# RH018_2.net
KiCad netlist of a schematic drawn in EAGLE
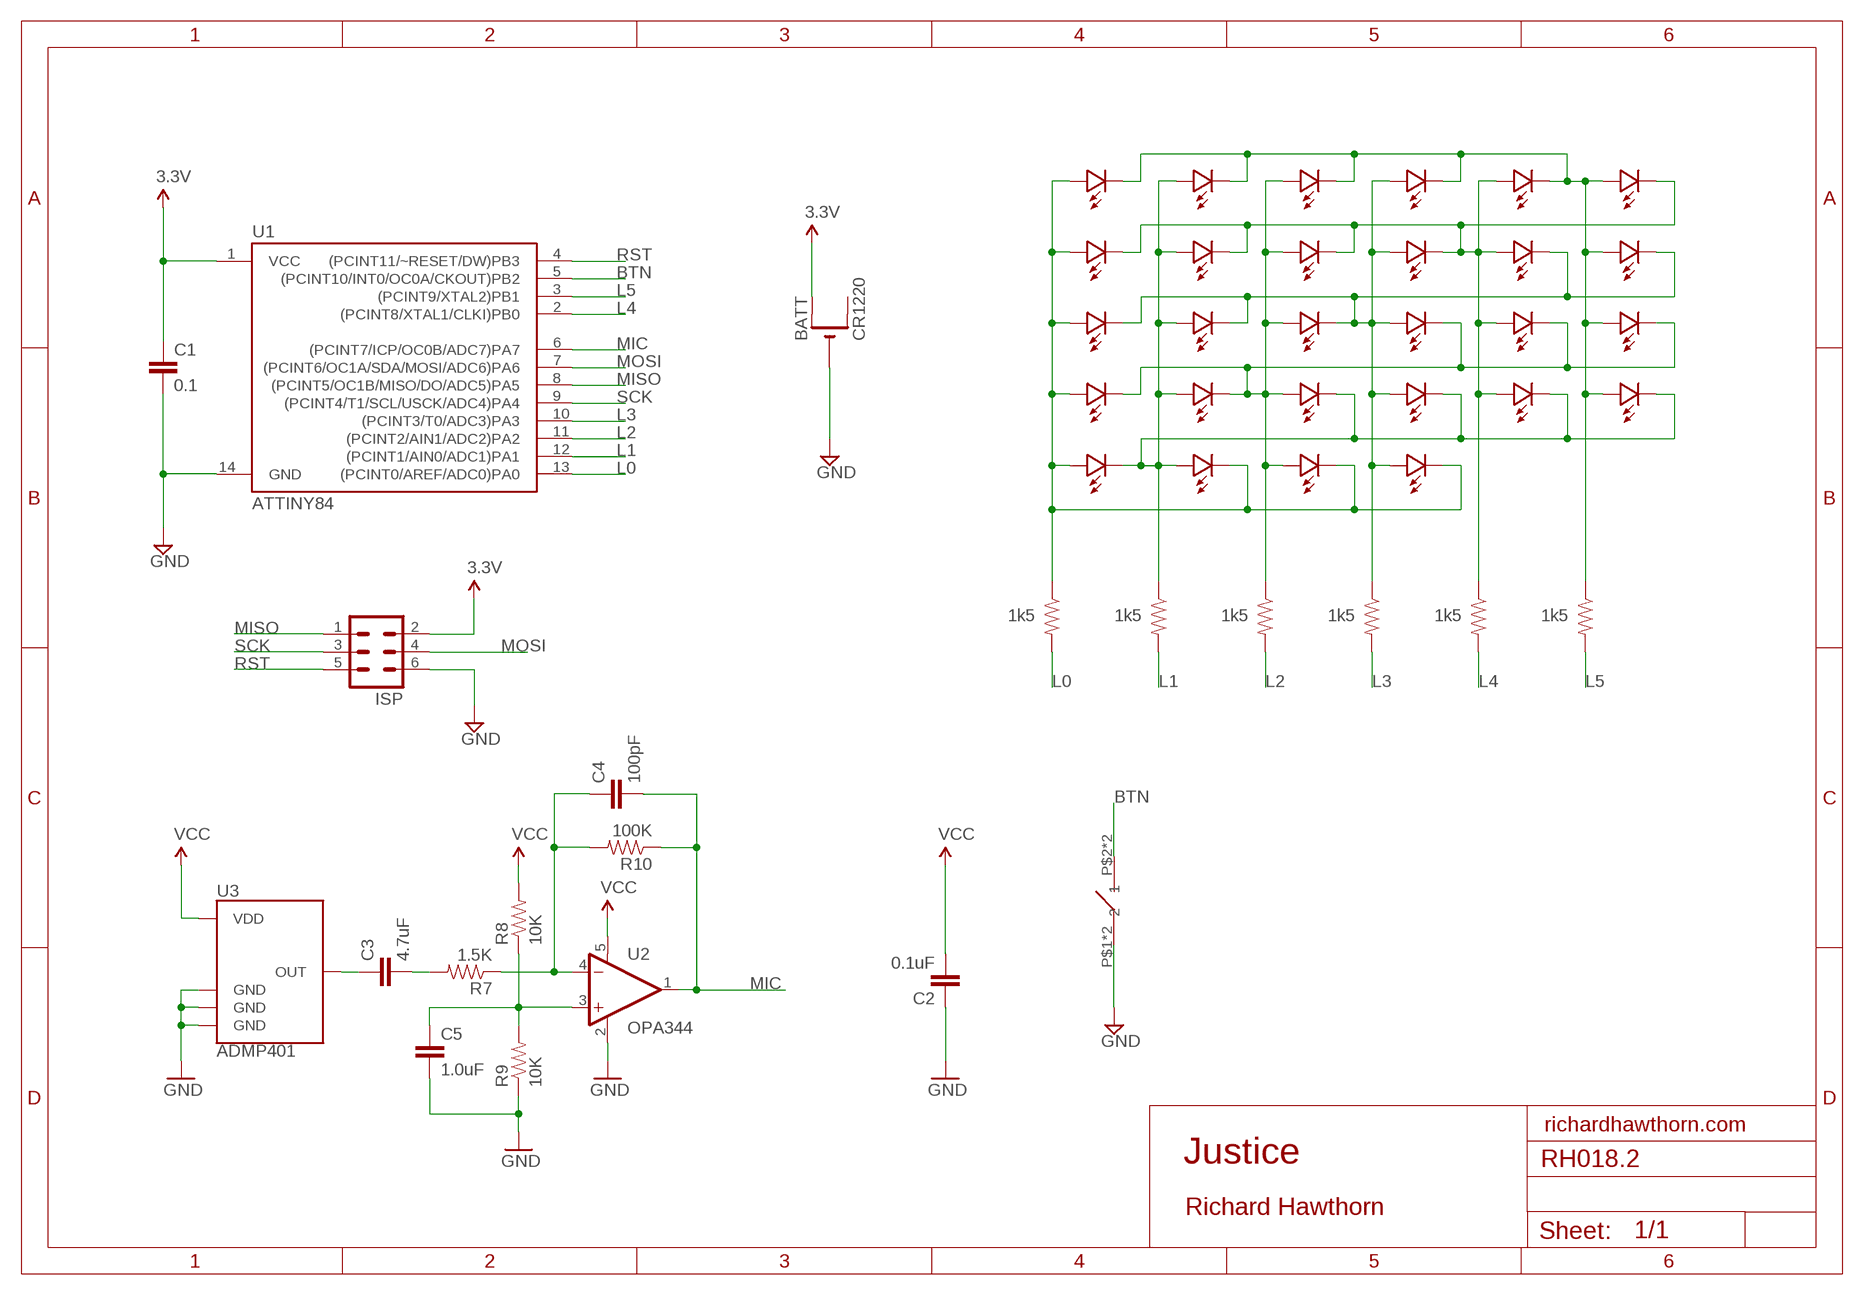
[diagram p0: schematic, sheet 1]

(export (version "E")
  (design (tool "Eeschema 10.0.6"))
  (components
    (comp (ref "BATT")
      (value "CR1220")
      (footprint "eagle-import:CR1220-SMD")
      (libsource (lib "eagle-import") (part "CR1220SMT"))
    )
    (comp (ref "BTN1")
      (value "TURTLE-3PIN")
      (footprint "eagle-import:TURTLE-3PIN")
      (libsource (lib "eagle-import") (part "TURTLE-3PIN"))
    )
    (comp (ref "C1")
      (value "0.1")
      (footprint "eagle-import:0603-CAP")
      (libsource (lib "eagle-import") (part "CAP0603-CAP"))
    )
    (comp (ref "C2")
      (value "0.1uF")
      (footprint "eagle-import:0402-CAP")
      (libsource (lib "eagle-import") (part "SparkFun_CAP0402-CAP"))
    )
    (comp (ref "C3")
      (value "4.7uF")
      (footprint "eagle-import:0402-CAP")
      (libsource (lib "eagle-import") (part "SparkFun_CAP0402-CAP"))
    )
    (comp (ref "C4")
      (value "100pF")
      (footprint "eagle-import:0402-CAP")
      (libsource (lib "eagle-import") (part "SparkFun_CAP0402-CAP"))
    )
    (comp (ref "C5")
      (value "1.0uF")
      (footprint "eagle-import:0402-CAP")
      (libsource (lib "eagle-import") (part "SparkFun_CAP0402-CAP"))
    )
    (comp (ref "ISP")
      (value "MA03-2")
      (footprint "eagle-import:MA03-2")
      (libsource (lib "eagle-import") (part "MA03-2"))
    )
    (comp (ref "LED1")
      (value "LED0603")
      (footprint "eagle-import:0603-LED")
      (libsource (lib "eagle-import") (part "LED0603"))
    )
    (comp (ref "LED2")
      (value "LED0603")
      (footprint "eagle-import:0603-LED")
      (libsource (lib "eagle-import") (part "LED0603"))
    )
    (comp (ref "LED3")
      (value "LED0603")
      (footprint "eagle-import:0603-LED")
      (libsource (lib "eagle-import") (part "LED0603"))
    )
    (comp (ref "LED4")
      (value "LED0603")
      (footprint "eagle-import:0603-LED")
      (libsource (lib "eagle-import") (part "LED0603"))
    )
    (comp (ref "LED5")
      (value "LED0603")
      (footprint "eagle-import:0603-LED")
      (libsource (lib "eagle-import") (part "LED0603"))
    )
    (comp (ref "LED6")
      (value "LED0603")
      (footprint "eagle-import:0603-LED")
      (libsource (lib "eagle-import") (part "LED0603"))
    )
    (comp (ref "LED7")
      (value "LED0603")
      (footprint "eagle-import:0603-LED")
      (libsource (lib "eagle-import") (part "LED0603"))
    )
    (comp (ref "LED8")
      (value "LED0603")
      (footprint "eagle-import:0603-LED")
      (libsource (lib "eagle-import") (part "LED0603"))
    )
    (comp (ref "LED9")
      (value "LED0603")
      (footprint "eagle-import:0603-LED")
      (libsource (lib "eagle-import") (part "LED0603"))
    )
    (comp (ref "LED10")
      (value "LED0603")
      (footprint "eagle-import:0603-LED")
      (libsource (lib "eagle-import") (part "LED0603"))
    )
    (comp (ref "LED11")
      (value "LED0603")
      (footprint "eagle-import:0603-LED")
      (libsource (lib "eagle-import") (part "LED0603"))
    )
    (comp (ref "LED12")
      (value "LED0603")
      (footprint "eagle-import:0603-LED")
      (libsource (lib "eagle-import") (part "LED0603"))
    )
    (comp (ref "LED13")
      (value "LED0603")
      (footprint "eagle-import:0603-LED")
      (libsource (lib "eagle-import") (part "LED0603"))
    )
    (comp (ref "LED14")
      (value "LED0603")
      (footprint "eagle-import:0603-LED")
      (libsource (lib "eagle-import") (part "LED0603"))
    )
    (comp (ref "LED15")
      (value "LED0603")
      (footprint "eagle-import:0603-LED")
      (libsource (lib "eagle-import") (part "LED0603"))
    )
    (comp (ref "LED16")
      (value "LED0603")
      (footprint "eagle-import:0603-LED")
      (libsource (lib "eagle-import") (part "LED0603"))
    )
    (comp (ref "LED17")
      (value "LED0603")
      (footprint "eagle-import:0603-LED")
      (libsource (lib "eagle-import") (part "LED0603"))
    )
    (comp (ref "LED18")
      (value "LED0603")
      (footprint "eagle-import:0603-LED")
      (libsource (lib "eagle-import") (part "LED0603"))
    )
    (comp (ref "LED19")
      (value "LED0603")
      (footprint "eagle-import:0603-LED")
      (libsource (lib "eagle-import") (part "LED0603"))
    )
    (comp (ref "LED20")
      (value "LED0603")
      (footprint "eagle-import:0603-LED")
      (libsource (lib "eagle-import") (part "LED0603"))
    )
    (comp (ref "LED21")
      (value "LED0603")
      (footprint "eagle-import:0603-LED")
      (libsource (lib "eagle-import") (part "LED0603"))
    )
    (comp (ref "LED22")
      (value "LED0603")
      (footprint "eagle-import:0603-LED")
      (libsource (lib "eagle-import") (part "LED0603"))
    )
    (comp (ref "LED23")
      (value "LED0603")
      (footprint "eagle-import:0603-LED")
      (libsource (lib "eagle-import") (part "LED0603"))
    )
    (comp (ref "LED24")
      (value "LED0603")
      (footprint "eagle-import:0603-LED")
      (libsource (lib "eagle-import") (part "LED0603"))
    )
    (comp (ref "LED25")
      (value "LED0603")
      (footprint "eagle-import:0603-LED")
      (libsource (lib "eagle-import") (part "LED0603"))
    )
    (comp (ref "LED26")
      (value "LED0603")
      (footprint "eagle-import:0603-LED")
      (libsource (lib "eagle-import") (part "LED0603"))
    )
    (comp (ref "LED27")
      (value "LED0603")
      (footprint "eagle-import:0603-LED")
      (libsource (lib "eagle-import") (part "LED0603"))
    )
    (comp (ref "LED28")
      (value "LED0603")
      (footprint "eagle-import:0603-LED")
      (libsource (lib "eagle-import") (part "LED0603"))
    )
    (comp (ref "R1")
      (value "1k5")
      (footprint "eagle-import:0603-RES")
      (libsource (lib "eagle-import") (part "RESISTOR0603-RES"))
    )
    (comp (ref "R2")
      (value "1k5")
      (footprint "eagle-import:0603-RES")
      (libsource (lib "eagle-import") (part "RESISTOR0603-RES"))
    )
    (comp (ref "R3")
      (value "1k5")
      (footprint "eagle-import:0603-RES")
      (libsource (lib "eagle-import") (part "RESISTOR0603-RES"))
    )
    (comp (ref "R4")
      (value "1k5")
      (footprint "eagle-import:0603-RES")
      (libsource (lib "eagle-import") (part "RESISTOR0603-RES"))
    )
    (comp (ref "R5")
      (value "1k5")
      (footprint "eagle-import:0603-RES")
      (libsource (lib "eagle-import") (part "RESISTOR0603-RES"))
    )
    (comp (ref "R6")
      (value "1k5")
      (footprint "eagle-import:0603-RES")
      (libsource (lib "eagle-import") (part "RESISTOR0603-RES"))
    )
    (comp (ref "R7")
      (value "1.5K")
      (footprint "eagle-import:0402-RES")
      (libsource (lib "eagle-import") (part "SparkFun_RESISTOR0402-RES"))
    )
    (comp (ref "R8")
      (value "10K")
      (footprint "eagle-import:0402-RES")
      (libsource (lib "eagle-import") (part "SparkFun_RESISTOR0402-RES"))
    )
    (comp (ref "R9")
      (value "10K")
      (footprint "eagle-import:0402-RES")
      (libsource (lib "eagle-import") (part "SparkFun_RESISTOR0402-RES"))
    )
    (comp (ref "R10")
      (value "100K")
      (footprint "eagle-import:0402-RES")
      (libsource (lib "eagle-import") (part "SparkFun_RESISTOR0402-RES"))
    )
    (comp (ref "U1")
      (value "ATTINY84")
      (footprint "eagle-import:SO14")
      (libsource (lib "eagle-import") (part "ATTINY84"))
    )
    (comp (ref "U2")
      (value "OPA344")
      (footprint "eagle-import:SOT23-5")
      (libsource (lib "eagle-import") (part "OPA344"))
    )
    (comp (ref "U3")
      (value "ADMP401")
      (footprint "eagle-import:ADMP401")
      (libsource (lib "eagle-import") (part "ADMP401"))
    )
  )
  (nets
    (net (code "1") (name "/BTN") (class "Default")
      (node (ref "BTN1") (pin "P$2") (pinfunction "2_P$2") (pintype "bidirectional"))
      (node (ref "BTN1") (pin "P$4") (pinfunction "2_P$4") (pintype "bidirectional"))
      (node (ref "U1") (pin "5") (pinfunction "(PCINT10/INT0/OC0A/CKOUT)PB2_5") (pintype "bidirectional"))
    )
    (net (code "2") (name "/L0") (class "Default")
      (node (ref "R1") (pin "2") (pinfunction "2_2") (pintype "passive"))
      (node (ref "U1") (pin "13") (pinfunction "(PCINT0/AREF/ADC0)PA0_13") (pintype "bidirectional"))
    )
    (net (code "3") (name "/L1") (class "Default")
      (node (ref "R2") (pin "2") (pinfunction "2_2") (pintype "passive"))
      (node (ref "U1") (pin "12") (pinfunction "(PCINT1/AIN0/ADC1)PA1_12") (pintype "bidirectional"))
    )
    (net (code "4") (name "/L2") (class "Default")
      (node (ref "R3") (pin "2") (pinfunction "2_2") (pintype "passive"))
      (node (ref "U1") (pin "11") (pinfunction "(PCINT2/AIN1/ADC2)PA2_11") (pintype "bidirectional"))
    )
    (net (code "5") (name "/L3") (class "Default")
      (node (ref "R4") (pin "2") (pinfunction "2_2") (pintype "passive"))
      (node (ref "U1") (pin "10") (pinfunction "(PCINT3/T0/ADC3)PA3_10") (pintype "bidirectional"))
    )
    (net (code "6") (name "/L4") (class "Default")
      (node (ref "R5") (pin "2") (pinfunction "2_2") (pintype "passive"))
      (node (ref "U1") (pin "2") (pinfunction "(PCINT8/XTAL1/CLKI)PB0_2") (pintype "bidirectional"))
    )
    (net (code "7") (name "/L5") (class "Default")
      (node (ref "R6") (pin "2") (pinfunction "2_2") (pintype "passive"))
      (node (ref "U1") (pin "3") (pinfunction "(PCINT9/XTAL2)PB1_3") (pintype "bidirectional"))
    )
    (net (code "8") (name "/MIC") (class "Default")
      (node (ref "C4") (pin "2") (pinfunction "2_2") (pintype "passive"))
      (node (ref "R10") (pin "1") (pinfunction "1_1") (pintype "passive"))
      (node (ref "U1") (pin "6") (pinfunction "(PCINT7/ICP/OC0B/ADC7)PA7_6") (pintype "bidirectional"))
      (node (ref "U2") (pin "1") (pinfunction "OUT_1") (pintype "output"))
    )
    (net (code "9") (name "/MISO") (class "Default")
      (node (ref "ISP") (pin "1") (pinfunction "1_1") (pintype "passive"))
      (node (ref "U1") (pin "8") (pinfunction "(PCINT5/OC1B/MISO/DO/ADC5)PA5_8") (pintype "bidirectional"))
    )
    (net (code "10") (name "/MOSI") (class "Default")
      (node (ref "ISP") (pin "4") (pinfunction "4_4") (pintype "passive"))
      (node (ref "U1") (pin "7") (pinfunction "(PCINT6/OC1A/SDA/MOSI/ADC6)PA6_7") (pintype "bidirectional"))
    )
    (net (code "11") (name "/RST") (class "Default")
      (node (ref "ISP") (pin "5") (pinfunction "5_5") (pintype "passive"))
      (node (ref "U1") (pin "4") (pinfunction "(PCINT11/~{RESET/DW})PB3_4") (pintype "bidirectional"))
    )
    (net (code "12") (name "/SCK") (class "Default")
      (node (ref "ISP") (pin "3") (pinfunction "3_3") (pintype "passive"))
      (node (ref "U1") (pin "9") (pinfunction "(PCINT4/T1/SCL/USCK/ADC4)PA4_9") (pintype "bidirectional"))
    )
    (net (code "13") (name "3.3V") (class "Default")
      (node (ref "BATT") (pin "+$1") (pinfunction "+_+$1") (pintype "passive"))
      (node (ref "C1") (pin "1") (pinfunction "1_1") (pintype "passive"))
      (node (ref "C2") (pin "2") (pinfunction "2_2") (pintype "passive"))
      (node (ref "ISP") (pin "2") (pinfunction "2_2") (pintype "passive"))
      (node (ref "R8") (pin "2") (pinfunction "2_2") (pintype "passive"))
      (node (ref "U1") (pin "1") (pinfunction "VCC_1") (pintype "bidirectional"))
      (node (ref "U2") (pin "5") (pinfunction "V+_5") (pintype "power_in"))
      (node (ref "U3") (pin "5") (pinfunction "VDD_5") (pintype "bidirectional"))
    )
    (net (code "14") (name "GND") (class "Default")
      (node (ref "BATT") (pin "-") (pinfunction "-_-") (pintype "passive"))
      (node (ref "BTN1") (pin "P$1") (pinfunction "1_P$1") (pintype "bidirectional"))
      (node (ref "BTN1") (pin "P$3") (pinfunction "1_P$3") (pintype "bidirectional"))
      (node (ref "C1") (pin "2") (pinfunction "2_2") (pintype "passive"))
      (node (ref "C2") (pin "1") (pinfunction "1_1") (pintype "passive"))
      (node (ref "C5") (pin "2") (pinfunction "2_2") (pintype "passive"))
      (node (ref "ISP") (pin "6") (pinfunction "6_6") (pintype "passive"))
      (node (ref "R9") (pin "1") (pinfunction "1_1") (pintype "passive"))
      (node (ref "U1") (pin "14") (pinfunction "GND_14") (pintype "bidirectional"))
      (node (ref "U2") (pin "2") (pinfunction "V-_2") (pintype "power_in"))
      (node (ref "U3") (pin "2") (pinfunction "GND_2") (pintype "bidirectional"))
      (node (ref "U3") (pin "4") (pinfunction "GND_4") (pintype "bidirectional"))
      (node (ref "U3") (pin "6") (pinfunction "GND_6") (pintype "bidirectional"))
    )
    (net (code "15") (name "Net-(C3-Pad2)") (class "Default")
      (node (ref "C3") (pin "2") (pinfunction "2_2") (pintype "passive"))
      (node (ref "R7") (pin "2") (pinfunction "2_2") (pintype "passive"))
    )
    (net (code "16") (name "Net-(LED1-PadMINUS)") (class "Default")
      (node (ref "LED1") (pin "MINUS") (pinfunction "MINUS_MINUS") (pintype "passive"))
      (node (ref "LED12") (pin "PLUS") (pinfunction "PLUS_PLUS") (pintype "passive"))
      (node (ref "LED18") (pin "PLUS") (pinfunction "PLUS_PLUS") (pintype "passive"))
      (node (ref "LED2") (pin "MINUS") (pinfunction "MINUS_MINUS") (pintype "passive"))
      (node (ref "LED24") (pin "PLUS") (pinfunction "PLUS_PLUS") (pintype "passive"))
      (node (ref "LED3") (pin "MINUS") (pinfunction "MINUS_MINUS") (pintype "passive"))
      (node (ref "LED4") (pin "MINUS") (pinfunction "MINUS_MINUS") (pintype "passive"))
      (node (ref "LED5") (pin "MINUS") (pinfunction "MINUS_MINUS") (pintype "passive"))
      (node (ref "LED6") (pin "PLUS") (pinfunction "PLUS_PLUS") (pintype "passive"))
      (node (ref "R6") (pin "1") (pinfunction "1_1") (pintype "passive"))
    )
    (net (code "17") (name "Net-(LED1-PadPLUS)") (class "Default")
      (node (ref "LED1") (pin "PLUS") (pinfunction "PLUS_PLUS") (pintype "passive"))
      (node (ref "LED13") (pin "PLUS") (pinfunction "PLUS_PLUS") (pintype "passive"))
      (node (ref "LED19") (pin "PLUS") (pinfunction "PLUS_PLUS") (pintype "passive"))
      (node (ref "LED25") (pin "PLUS") (pinfunction "PLUS_PLUS") (pintype "passive"))
      (node (ref "LED26") (pin "MINUS") (pinfunction "MINUS_MINUS") (pintype "passive"))
      (node (ref "LED27") (pin "MINUS") (pinfunction "MINUS_MINUS") (pintype "passive"))
      (node (ref "LED28") (pin "MINUS") (pinfunction "MINUS_MINUS") (pintype "passive"))
      (node (ref "LED7") (pin "PLUS") (pinfunction "PLUS_PLUS") (pintype "passive"))
      (node (ref "R1") (pin "1") (pinfunction "1_1") (pintype "passive"))
    )
    (net (code "18") (name "Net-(LED10-PadMINUS)") (class "Default")
      (node (ref "LED10") (pin "MINUS") (pinfunction "MINUS_MINUS") (pintype "passive"))
      (node (ref "LED11") (pin "PLUS") (pinfunction "PLUS_PLUS") (pintype "passive"))
      (node (ref "LED17") (pin "PLUS") (pinfunction "PLUS_PLUS") (pintype "passive"))
      (node (ref "LED23") (pin "PLUS") (pinfunction "PLUS_PLUS") (pintype "passive"))
      (node (ref "LED5") (pin "PLUS") (pinfunction "PLUS_PLUS") (pintype "passive"))
      (node (ref "LED6") (pin "MINUS") (pinfunction "MINUS_MINUS") (pintype "passive"))
      (node (ref "LED7") (pin "MINUS") (pinfunction "MINUS_MINUS") (pintype "passive"))
      (node (ref "LED8") (pin "MINUS") (pinfunction "MINUS_MINUS") (pintype "passive"))
      (node (ref "LED9") (pin "MINUS") (pinfunction "MINUS_MINUS") (pintype "passive"))
      (node (ref "R5") (pin "1") (pinfunction "1_1") (pintype "passive"))
    )
    (net (code "19") (name "Net-(LED10-PadPLUS)") (class "Default")
      (node (ref "LED10") (pin "PLUS") (pinfunction "PLUS_PLUS") (pintype "passive"))
      (node (ref "LED11") (pin "MINUS") (pinfunction "MINUS_MINUS") (pintype "passive"))
      (node (ref "LED12") (pin "MINUS") (pinfunction "MINUS_MINUS") (pintype "passive"))
      (node (ref "LED13") (pin "MINUS") (pinfunction "MINUS_MINUS") (pintype "passive"))
      (node (ref "LED14") (pin "MINUS") (pinfunction "MINUS_MINUS") (pintype "passive"))
      (node (ref "LED15") (pin "MINUS") (pinfunction "MINUS_MINUS") (pintype "passive"))
      (node (ref "LED16") (pin "PLUS") (pinfunction "PLUS_PLUS") (pintype "passive"))
      (node (ref "LED22") (pin "PLUS") (pinfunction "PLUS_PLUS") (pintype "passive"))
      (node (ref "LED28") (pin "PLUS") (pinfunction "PLUS_PLUS") (pintype "passive"))
      (node (ref "LED4") (pin "PLUS") (pinfunction "PLUS_PLUS") (pintype "passive"))
      (node (ref "R4") (pin "1") (pinfunction "1_1") (pintype "passive"))
    )
    (net (code "20") (name "Net-(LED14-PadPLUS)") (class "Default")
      (node (ref "LED14") (pin "PLUS") (pinfunction "PLUS_PLUS") (pintype "passive"))
      (node (ref "LED2") (pin "PLUS") (pinfunction "PLUS_PLUS") (pintype "passive"))
      (node (ref "LED20") (pin "PLUS") (pinfunction "PLUS_PLUS") (pintype "passive"))
      (node (ref "LED21") (pin "MINUS") (pinfunction "MINUS_MINUS") (pintype "passive"))
      (node (ref "LED22") (pin "MINUS") (pinfunction "MINUS_MINUS") (pintype "passive"))
      (node (ref "LED23") (pin "MINUS") (pinfunction "MINUS_MINUS") (pintype "passive"))
      (node (ref "LED24") (pin "MINUS") (pinfunction "MINUS_MINUS") (pintype "passive"))
      (node (ref "LED25") (pin "MINUS") (pinfunction "MINUS_MINUS") (pintype "passive"))
      (node (ref "LED26") (pin "PLUS") (pinfunction "PLUS_PLUS") (pintype "passive"))
      (node (ref "LED8") (pin "PLUS") (pinfunction "PLUS_PLUS") (pintype "passive"))
      (node (ref "R2") (pin "1") (pinfunction "1_1") (pintype "passive"))
    )
    (net (code "21") (name "Net-(LED15-PadPLUS)") (class "Default")
      (node (ref "LED15") (pin "PLUS") (pinfunction "PLUS_PLUS") (pintype "passive"))
      (node (ref "LED16") (pin "MINUS") (pinfunction "MINUS_MINUS") (pintype "passive"))
      (node (ref "LED17") (pin "MINUS") (pinfunction "MINUS_MINUS") (pintype "passive"))
      (node (ref "LED18") (pin "MINUS") (pinfunction "MINUS_MINUS") (pintype "passive"))
      (node (ref "LED19") (pin "MINUS") (pinfunction "MINUS_MINUS") (pintype "passive"))
      (node (ref "LED20") (pin "MINUS") (pinfunction "MINUS_MINUS") (pintype "passive"))
      (node (ref "LED21") (pin "PLUS") (pinfunction "PLUS_PLUS") (pintype "passive"))
      (node (ref "LED27") (pin "PLUS") (pinfunction "PLUS_PLUS") (pintype "passive"))
      (node (ref "LED3") (pin "PLUS") (pinfunction "PLUS_PLUS") (pintype "passive"))
      (node (ref "LED9") (pin "PLUS") (pinfunction "PLUS_PLUS") (pintype "passive"))
      (node (ref "R3") (pin "1") (pinfunction "1_1") (pintype "passive"))
    )
    (net (code "22") (name "Net-(U2-+IN)") (class "Default")
      (node (ref "C5") (pin "1") (pinfunction "1_1") (pintype "passive"))
      (node (ref "R8") (pin "1") (pinfunction "1_1") (pintype "passive"))
      (node (ref "R9") (pin "2") (pinfunction "2_2") (pintype "passive"))
      (node (ref "U2") (pin "3") (pinfunction "+IN_3") (pintype "input"))
    )
    (net (code "23") (name "Net-(U2--IN)") (class "Default")
      (node (ref "C4") (pin "1") (pinfunction "1_1") (pintype "passive"))
      (node (ref "R10") (pin "2") (pinfunction "2_2") (pintype "passive"))
      (node (ref "R7") (pin "1") (pinfunction "1_1") (pintype "passive"))
      (node (ref "U2") (pin "4") (pinfunction "-IN_4") (pintype "input"))
    )
    (net (code "24") (name "Net-(U3-OUT)") (class "Default")
      (node (ref "C3") (pin "1") (pinfunction "1_1") (pintype "passive"))
      (node (ref "U3") (pin "1") (pinfunction "OUT_1") (pintype "bidirectional"))
    )
    (net (code "25") (name "unconnected-(BATT-+1-Pad+$2)") (class "Default")
      (node (ref "BATT") (pin "+$2") (pinfunction "+1_+$2") (pintype "passive"))
    )
  )
)
